# Oh_Cheat.net
KiCad netlist of a schematic drawn in EAGLE
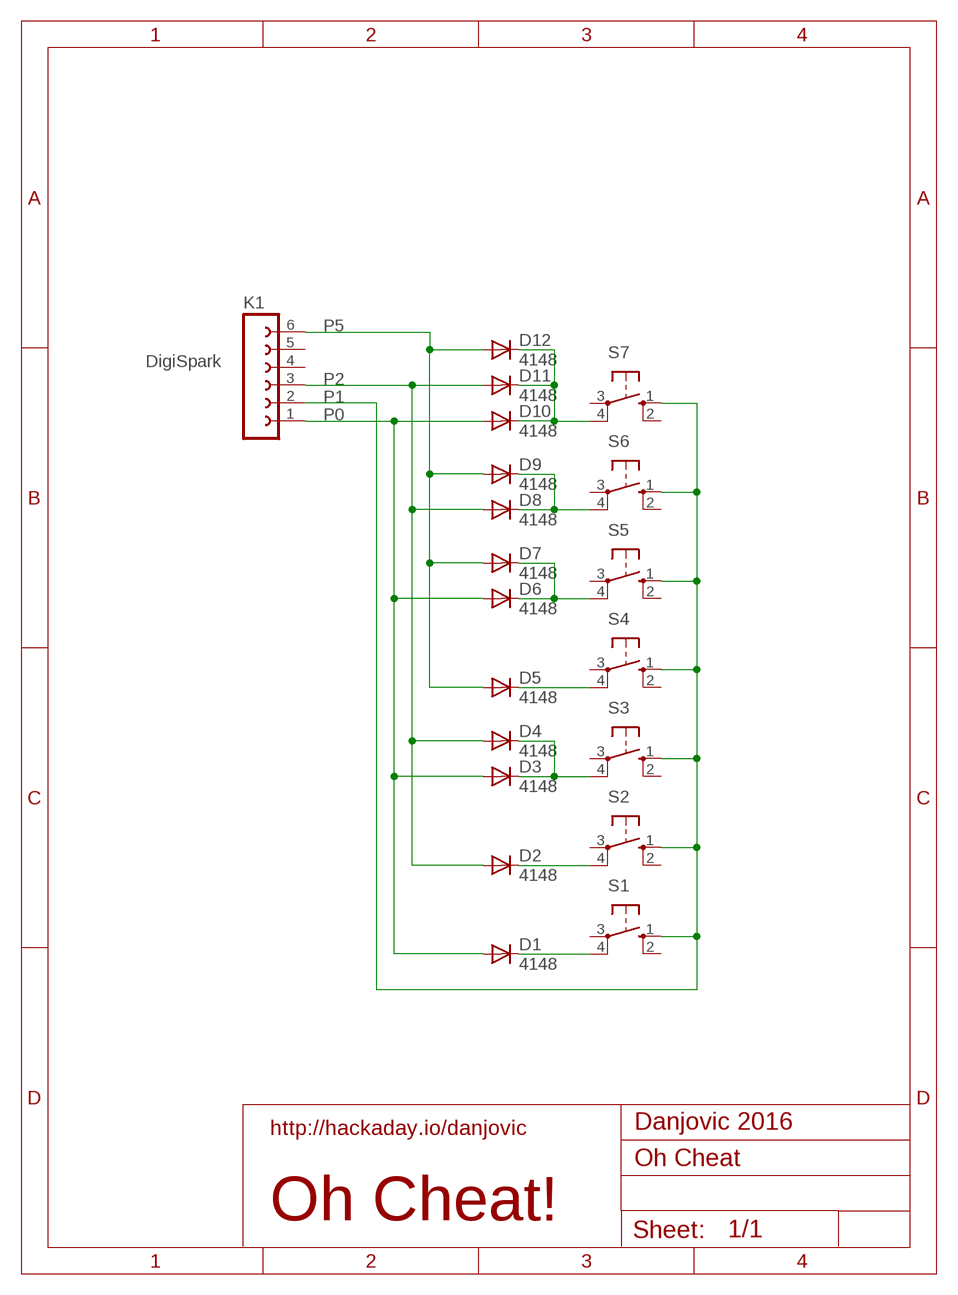
[diagram p0: schematic, sheet 1]

(export (version "E")
  (design (tool "Eeschema 10.0.6"))
  (components
    (comp (ref "D1")
      (value "4148")
      (footprint "eagle-import:DO35-7")
      (libsource (lib "eagle-import") (part "1N4148DO35-7"))
    )
    (comp (ref "D2")
      (value "4148")
      (footprint "eagle-import:DO35-7")
      (libsource (lib "eagle-import") (part "1N4148DO35-7"))
    )
    (comp (ref "D3")
      (value "4148")
      (footprint "eagle-import:DO35-7")
      (libsource (lib "eagle-import") (part "1N4148DO35-7"))
    )
    (comp (ref "D4")
      (value "4148")
      (footprint "eagle-import:DO35-7")
      (libsource (lib "eagle-import") (part "1N4148DO35-7"))
    )
    (comp (ref "D5")
      (value "4148")
      (footprint "eagle-import:DO35-7")
      (libsource (lib "eagle-import") (part "1N4148DO35-7"))
    )
    (comp (ref "D6")
      (value "4148")
      (footprint "eagle-import:DO35-7")
      (libsource (lib "eagle-import") (part "1N4148DO35-7"))
    )
    (comp (ref "D7")
      (value "4148")
      (footprint "eagle-import:DO35-7")
      (libsource (lib "eagle-import") (part "1N4148DO35-7"))
    )
    (comp (ref "D8")
      (value "4148")
      (footprint "eagle-import:DO35-7")
      (libsource (lib "eagle-import") (part "1N4148DO35-7"))
    )
    (comp (ref "D9")
      (value "4148")
      (footprint "eagle-import:DO35-7")
      (libsource (lib "eagle-import") (part "1N4148DO35-7"))
    )
    (comp (ref "D10")
      (value "4148")
      (footprint "eagle-import:DO35-7")
      (libsource (lib "eagle-import") (part "1N4148DO35-7"))
    )
    (comp (ref "D11")
      (value "4148")
      (footprint "eagle-import:DO35-7")
      (libsource (lib "eagle-import") (part "1N4148DO35-7"))
    )
    (comp (ref "D12")
      (value "4148")
      (footprint "eagle-import:DO35-7")
      (libsource (lib "eagle-import") (part "1N4148DO35-7"))
    )
    (comp (ref "K1")
      (value "FE06-1")
      (footprint "eagle-import:FE06")
      (libsource (lib "eagle-import") (part "FE06-1"))
    )
    (comp (ref "S1")
      (value "40-XX")
      (footprint "eagle-import:B3F-40XX")
      (fields (field (name "MF") "OMRON COMPONENTS USA") (field (name "MPN") "B3F-4000"))
      (libsource (lib "eagle-import") (part "40-XX"))
    )
    (comp (ref "S2")
      (value "40-XX")
      (footprint "eagle-import:B3F-40XX")
      (fields (field (name "MF") "OMRON COMPONENTS USA") (field (name "MPN") "B3F-4000"))
      (libsource (lib "eagle-import") (part "40-XX"))
    )
    (comp (ref "S3")
      (value "40-XX")
      (footprint "eagle-import:B3F-40XX")
      (fields (field (name "MF") "OMRON COMPONENTS USA") (field (name "MPN") "B3F-4000"))
      (libsource (lib "eagle-import") (part "40-XX"))
    )
    (comp (ref "S4")
      (value "40-XX")
      (footprint "eagle-import:B3F-40XX")
      (fields (field (name "MF") "OMRON COMPONENTS USA") (field (name "MPN") "B3F-4000"))
      (libsource (lib "eagle-import") (part "40-XX"))
    )
    (comp (ref "S5")
      (value "40-XX")
      (footprint "eagle-import:B3F-40XX")
      (fields (field (name "MF") "OMRON COMPONENTS USA") (field (name "MPN") "B3F-4000"))
      (libsource (lib "eagle-import") (part "40-XX"))
    )
    (comp (ref "S6")
      (value "40-XX")
      (footprint "eagle-import:B3F-40XX")
      (fields (field (name "MF") "OMRON COMPONENTS USA") (field (name "MPN") "B3F-4000"))
      (libsource (lib "eagle-import") (part "40-XX"))
    )
    (comp (ref "S7")
      (value "40-XX")
      (footprint "eagle-import:B3F-40XX")
      (fields (field (name "MF") "OMRON COMPONENTS USA") (field (name "MPN") "B3F-4000"))
      (libsource (lib "eagle-import") (part "40-XX"))
    )
  )
  (nets
    (net (code "1") (name "/P0") (class "Default")
      (node (ref "D1") (pin "A") (pinfunction "A_A") (pintype "passive"))
      (node (ref "D10") (pin "A") (pinfunction "A_A") (pintype "passive"))
      (node (ref "D3") (pin "A") (pinfunction "A_A") (pintype "passive"))
      (node (ref "D6") (pin "A") (pinfunction "A_A") (pintype "passive"))
      (node (ref "K1") (pin "1") (pinfunction "1_1") (pintype "passive"))
    )
    (net (code "2") (name "/P1") (class "Default")
      (node (ref "K1") (pin "2") (pinfunction "2_2") (pintype "passive"))
      (node (ref "S1") (pin "1") (pinfunction "S_1") (pintype "passive"))
      (node (ref "S2") (pin "1") (pinfunction "S_1") (pintype "passive"))
      (node (ref "S3") (pin "1") (pinfunction "S_1") (pintype "passive"))
      (node (ref "S4") (pin "1") (pinfunction "S_1") (pintype "passive"))
      (node (ref "S5") (pin "1") (pinfunction "S_1") (pintype "passive"))
      (node (ref "S6") (pin "1") (pinfunction "S_1") (pintype "passive"))
      (node (ref "S7") (pin "1") (pinfunction "S_1") (pintype "passive"))
    )
    (net (code "3") (name "/P2") (class "Default")
      (node (ref "D11") (pin "A") (pinfunction "A_A") (pintype "passive"))
      (node (ref "D2") (pin "A") (pinfunction "A_A") (pintype "passive"))
      (node (ref "D4") (pin "A") (pinfunction "A_A") (pintype "passive"))
      (node (ref "D8") (pin "A") (pinfunction "A_A") (pintype "passive"))
      (node (ref "K1") (pin "3") (pinfunction "3_3") (pintype "passive"))
    )
    (net (code "4") (name "/P5") (class "Default")
      (node (ref "D12") (pin "A") (pinfunction "A_A") (pintype "passive"))
      (node (ref "D5") (pin "A") (pinfunction "A_A") (pintype "passive"))
      (node (ref "D7") (pin "A") (pinfunction "A_A") (pintype "passive"))
      (node (ref "D9") (pin "A") (pinfunction "A_A") (pintype "passive"))
      (node (ref "K1") (pin "6") (pinfunction "6_6") (pintype "passive"))
    )
    (net (code "5") (name "Net-(S1-P1)") (class "Default")
      (node (ref "D1") (pin "C") (pinfunction "C_C") (pintype "passive"))
      (node (ref "S1") (pin "4") (pinfunction "P1_4") (pintype "passive"))
    )
    (net (code "6") (name "Net-(S2-P1)") (class "Default")
      (node (ref "D2") (pin "C") (pinfunction "C_C") (pintype "passive"))
      (node (ref "S2") (pin "4") (pinfunction "P1_4") (pintype "passive"))
    )
    (net (code "7") (name "Net-(S3-P1)") (class "Default")
      (node (ref "D3") (pin "C") (pinfunction "C_C") (pintype "passive"))
      (node (ref "D4") (pin "C") (pinfunction "C_C") (pintype "passive"))
      (node (ref "S3") (pin "4") (pinfunction "P1_4") (pintype "passive"))
    )
    (net (code "8") (name "Net-(S4-P1)") (class "Default")
      (node (ref "D5") (pin "C") (pinfunction "C_C") (pintype "passive"))
      (node (ref "S4") (pin "4") (pinfunction "P1_4") (pintype "passive"))
    )
    (net (code "9") (name "Net-(S5-P1)") (class "Default")
      (node (ref "D6") (pin "C") (pinfunction "C_C") (pintype "passive"))
      (node (ref "D7") (pin "C") (pinfunction "C_C") (pintype "passive"))
      (node (ref "S5") (pin "4") (pinfunction "P1_4") (pintype "passive"))
    )
    (net (code "10") (name "Net-(S6-P1)") (class "Default")
      (node (ref "D8") (pin "C") (pinfunction "C_C") (pintype "passive"))
      (node (ref "D9") (pin "C") (pinfunction "C_C") (pintype "passive"))
      (node (ref "S6") (pin "4") (pinfunction "P1_4") (pintype "passive"))
    )
    (net (code "11") (name "Net-(S7-P1)") (class "Default")
      (node (ref "D10") (pin "C") (pinfunction "C_C") (pintype "passive"))
      (node (ref "D11") (pin "C") (pinfunction "C_C") (pintype "passive"))
      (node (ref "D12") (pin "C") (pinfunction "C_C") (pintype "passive"))
      (node (ref "S7") (pin "4") (pinfunction "P1_4") (pintype "passive"))
    )
    (net (code "12") (name "unconnected-(K1-Pad4)") (class "Default")
      (node (ref "K1") (pin "4") (pinfunction "4_4") (pintype "passive"))
    )
    (net (code "13") (name "unconnected-(K1-Pad5)") (class "Default")
      (node (ref "K1") (pin "5") (pinfunction "5_5") (pintype "passive"))
    )
    (net (code "14") (name "unconnected-(S1-P-Pad3)") (class "Default")
      (node (ref "S1") (pin "3") (pinfunction "P_3") (pintype "passive"))
    )
    (net (code "15") (name "unconnected-(S1-S1-Pad2)") (class "Default")
      (node (ref "S1") (pin "2") (pinfunction "S1_2") (pintype "passive"))
    )
    (net (code "16") (name "unconnected-(S2-P-Pad3)") (class "Default")
      (node (ref "S2") (pin "3") (pinfunction "P_3") (pintype "passive"))
    )
    (net (code "17") (name "unconnected-(S2-S1-Pad2)") (class "Default")
      (node (ref "S2") (pin "2") (pinfunction "S1_2") (pintype "passive"))
    )
    (net (code "18") (name "unconnected-(S3-P-Pad3)") (class "Default")
      (node (ref "S3") (pin "3") (pinfunction "P_3") (pintype "passive"))
    )
    (net (code "19") (name "unconnected-(S3-S1-Pad2)") (class "Default")
      (node (ref "S3") (pin "2") (pinfunction "S1_2") (pintype "passive"))
    )
    (net (code "20") (name "unconnected-(S4-P-Pad3)") (class "Default")
      (node (ref "S4") (pin "3") (pinfunction "P_3") (pintype "passive"))
    )
    (net (code "21") (name "unconnected-(S4-S1-Pad2)") (class "Default")
      (node (ref "S4") (pin "2") (pinfunction "S1_2") (pintype "passive"))
    )
    (net (code "22") (name "unconnected-(S5-P-Pad3)") (class "Default")
      (node (ref "S5") (pin "3") (pinfunction "P_3") (pintype "passive"))
    )
    (net (code "23") (name "unconnected-(S5-S1-Pad2)") (class "Default")
      (node (ref "S5") (pin "2") (pinfunction "S1_2") (pintype "passive"))
    )
    (net (code "24") (name "unconnected-(S6-P-Pad3)") (class "Default")
      (node (ref "S6") (pin "3") (pinfunction "P_3") (pintype "passive"))
    )
    (net (code "25") (name "unconnected-(S6-S1-Pad2)") (class "Default")
      (node (ref "S6") (pin "2") (pinfunction "S1_2") (pintype "passive"))
    )
    (net (code "26") (name "unconnected-(S7-P-Pad3)") (class "Default")
      (node (ref "S7") (pin "3") (pinfunction "P_3") (pintype "passive"))
    )
    (net (code "27") (name "unconnected-(S7-S1-Pad2)") (class "Default")
      (node (ref "S7") (pin "2") (pinfunction "S1_2") (pintype "passive"))
    )
  )
)
